# power_dist.net
KiCad netlist of a schematic drawn in EAGLE
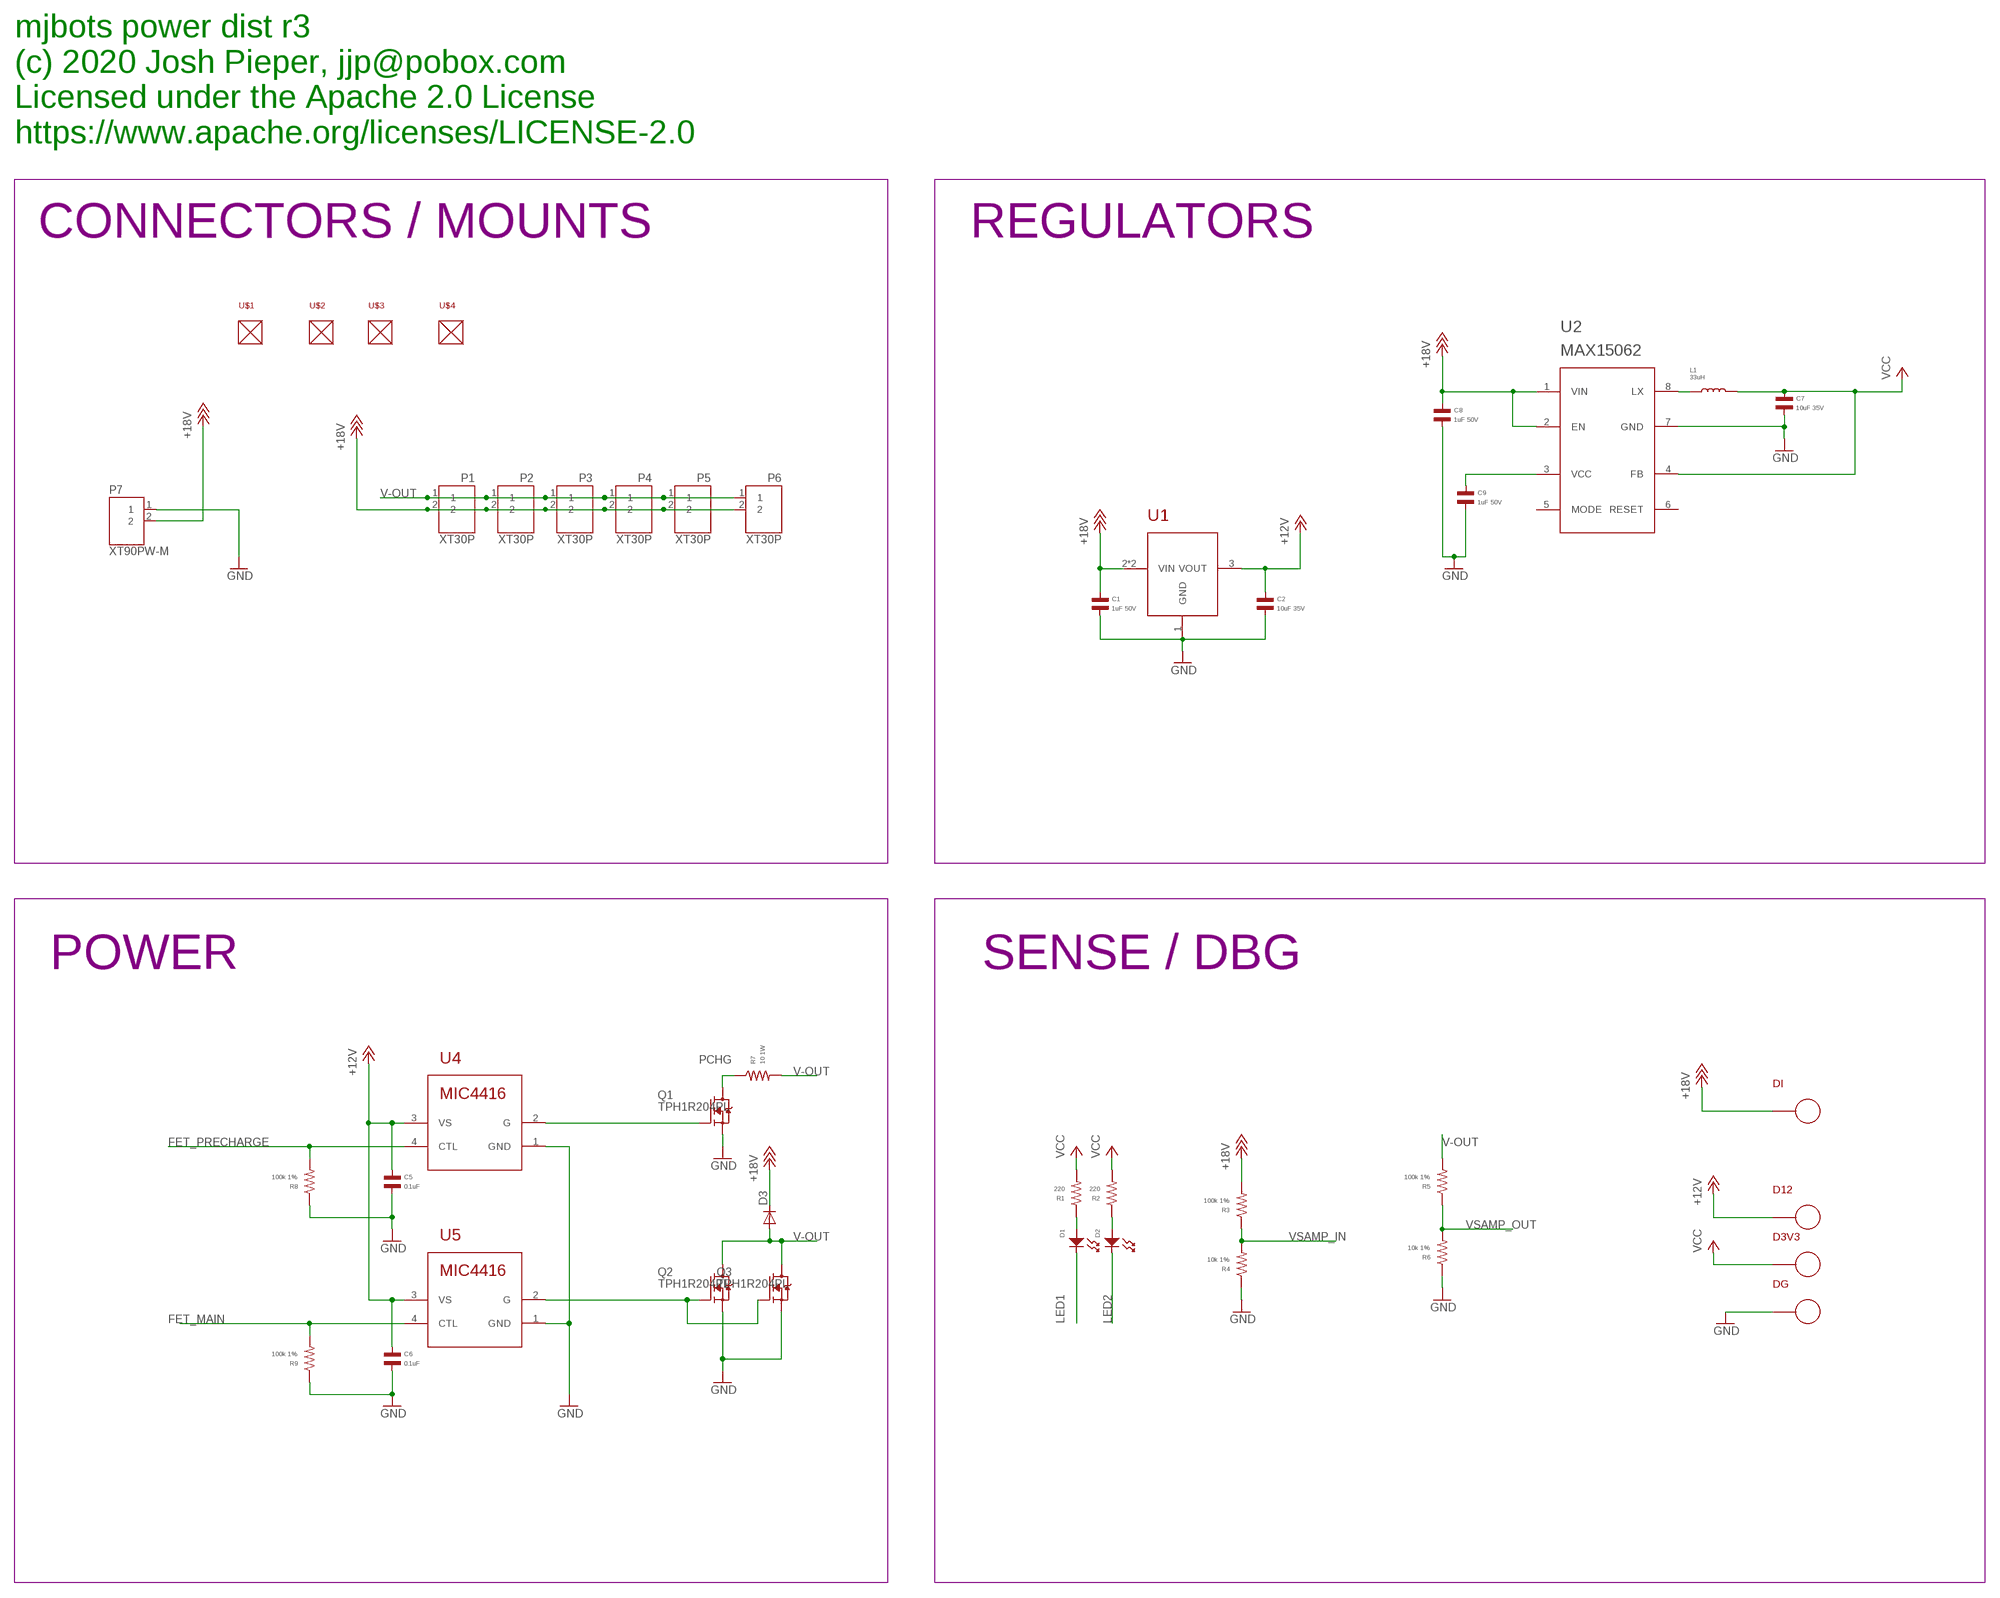
[diagram p0: schematic, sheet 1, part 1 of 2]
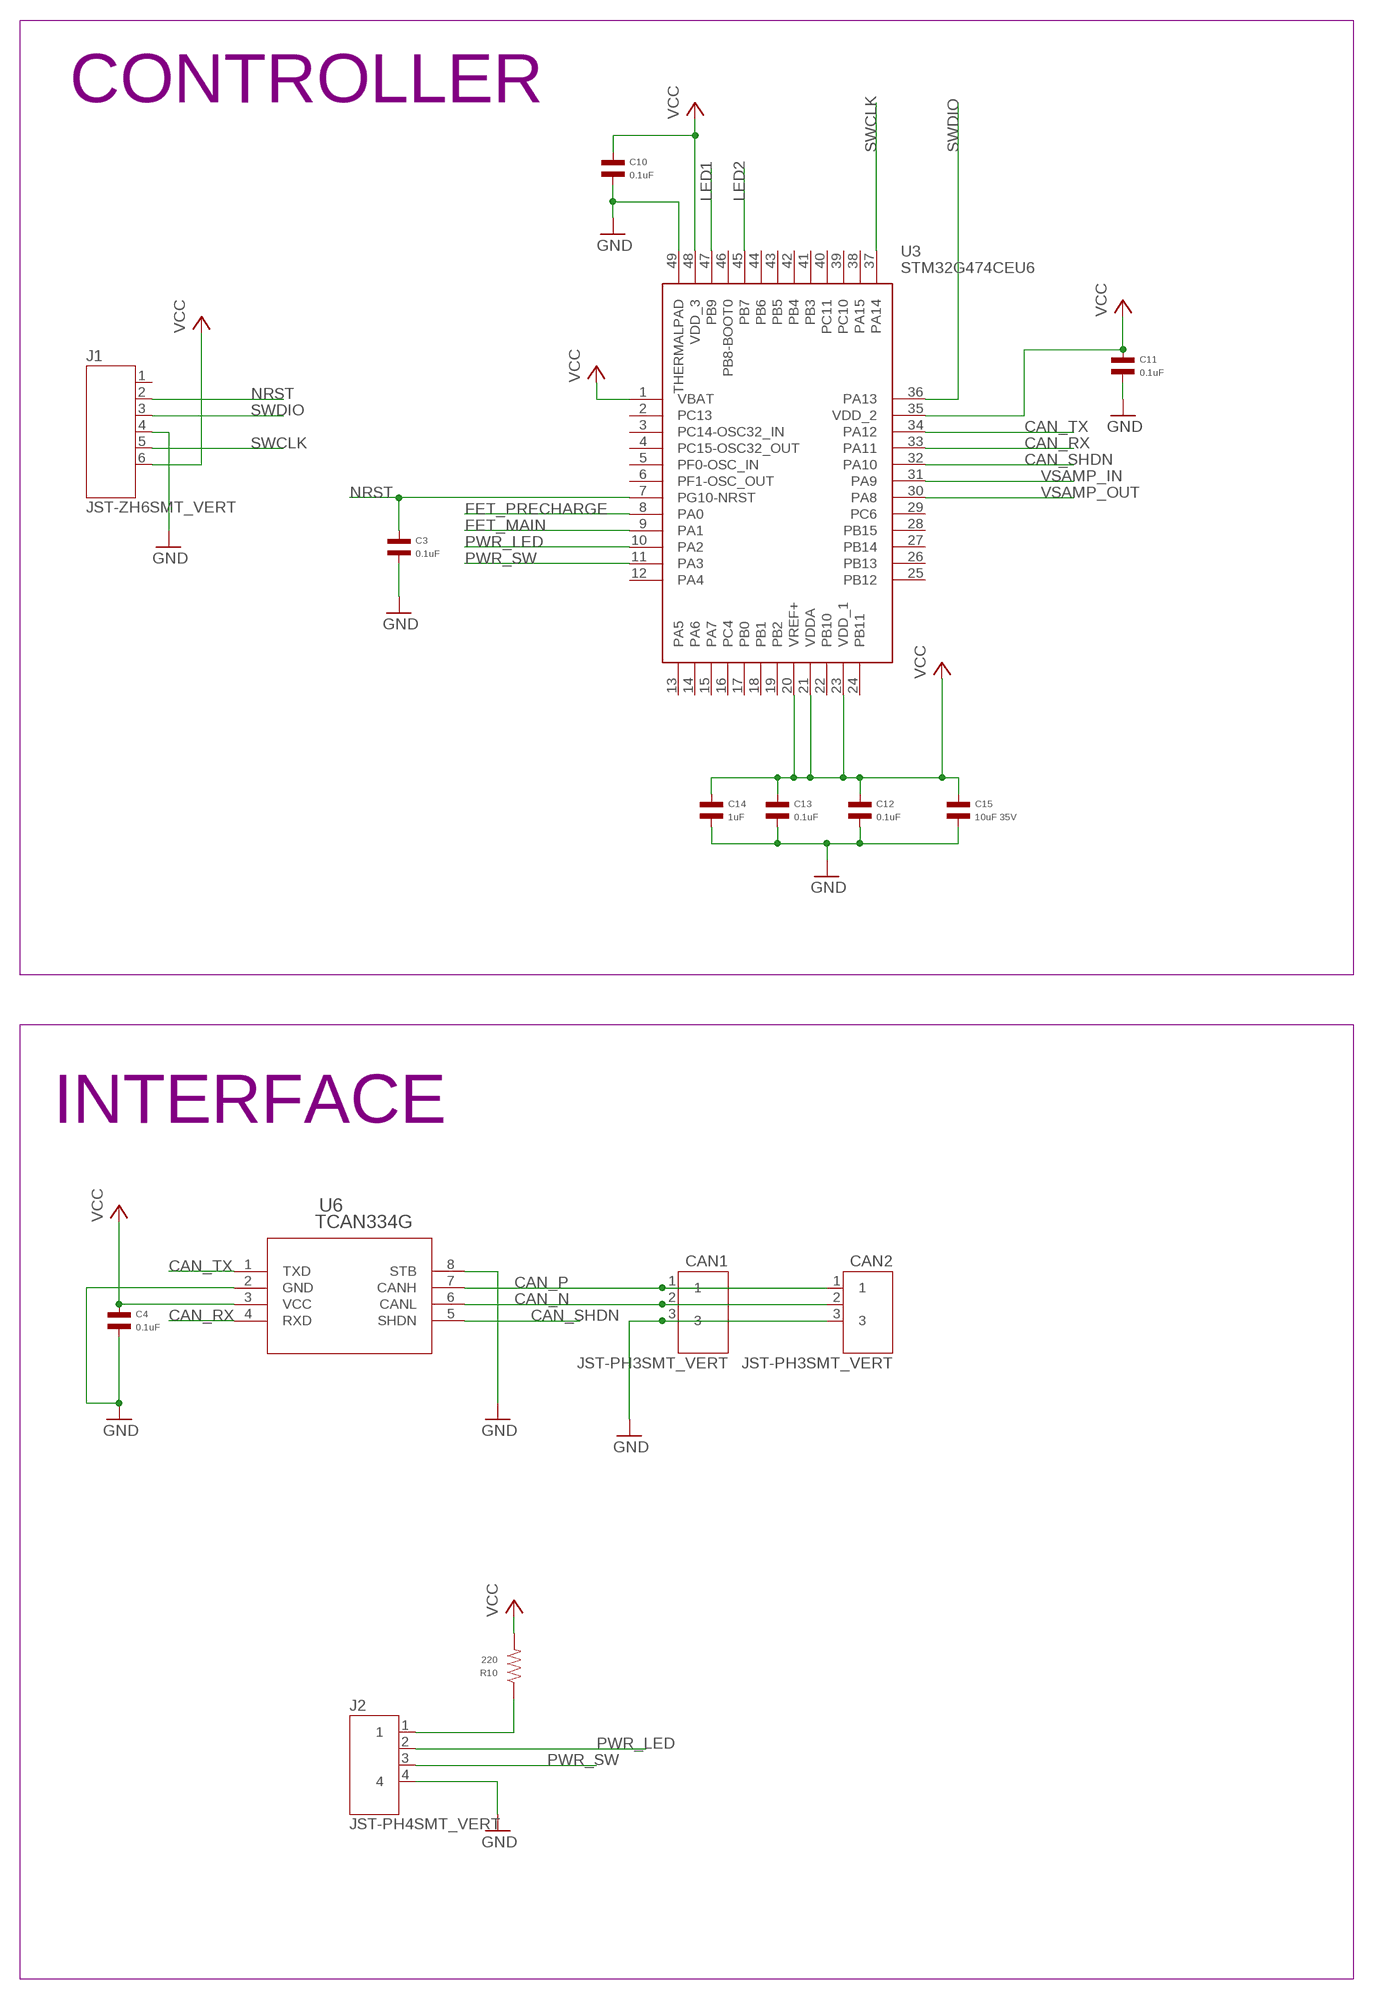
[diagram p1: schematic, sheet 1, part 2 of 2]

(export (version "E")
  (design (tool "Eeschema 10.0.6"))
  (components
    (comp (ref "C1")
      (value "1uF 50V")
      (footprint "eagle-import:C0603")
      (fields (field (name "MF") "SAMSUNG") (field (name "MPN") "CL10A105KB8NNNC"))
      (libsource (lib "eagle-import") (part "CAPACITOR_NP_0603"))
    )
    (comp (ref "C2")
      (value "10uF 35V")
      (footprint "eagle-import:C1206")
      (fields (field (name "MF") "TDK") (field (name "MPN") "CGA5L1X7R1V106K160AC"))
      (libsource (lib "eagle-import") (part "CAPACITOR_NP_1206"))
    )
    (comp (ref "C3")
      (value "0.1uF")
      (footprint "eagle-import:C0402")
      (fields (field (name "HOUSEPART") "1") (field (name "MPN") "MF-CAP-0402-0.1uF"))
      (libsource (lib "eagle-import") (part "CAPACITOR_NP_0402"))
    )
    (comp (ref "C4")
      (value "0.1uF")
      (footprint "eagle-import:C0402")
      (fields (field (name "HOUSEPART") "1") (field (name "MPN") "MF-CAP-0402-0.1uF"))
      (libsource (lib "eagle-import") (part "CAPACITOR_NP_0402"))
    )
    (comp (ref "C5")
      (value "0.1uF")
      (footprint "eagle-import:C0402")
      (fields (field (name "HOUSEPART") "1") (field (name "MPN") "MF-CAP-0402-0.1uF"))
      (libsource (lib "eagle-import") (part "CAPACITOR_NP_0402"))
    )
    (comp (ref "C6")
      (value "0.1uF")
      (footprint "eagle-import:C0402")
      (fields (field (name "HOUSEPART") "1") (field (name "MPN") "MF-CAP-0402-0.1uF"))
      (libsource (lib "eagle-import") (part "CAPACITOR_NP_0402"))
    )
    (comp (ref "C7")
      (value "10uF 35V")
      (footprint "eagle-import:C1206")
      (fields (field (name "MF") "TDK") (field (name "MPN") "CGA5L1X7R1V106K160AC"))
      (libsource (lib "eagle-import") (part "CAPACITOR_NP_1206"))
    )
    (comp (ref "C8")
      (value "1uF 50V")
      (footprint "eagle-import:C0603")
      (fields (field (name "MF") "SAMSUNG") (field (name "MPN") "CL10A105KB8NNNC"))
      (libsource (lib "eagle-import") (part "CAPACITOR_NP_0603"))
    )
    (comp (ref "C9")
      (value "1uF 50V")
      (footprint "eagle-import:C0603")
      (fields (field (name "MF") "SAMSUNG") (field (name "MPN") "CL10A105KB8NNNC"))
      (libsource (lib "eagle-import") (part "CAPACITOR_NP_0603"))
    )
    (comp (ref "C10")
      (value "0.1uF")
      (footprint "eagle-import:C0402")
      (fields (field (name "HOUSEPART") "1") (field (name "MPN") "MF-CAP-0402-0.1uF"))
      (libsource (lib "eagle-import") (part "CAPACITOR_NP_0402"))
    )
    (comp (ref "C11")
      (value "0.1uF")
      (footprint "eagle-import:C0402")
      (fields (field (name "HOUSEPART") "1") (field (name "MPN") "MF-CAP-0402-0.1uF"))
      (libsource (lib "eagle-import") (part "CAPACITOR_NP_0402"))
    )
    (comp (ref "C12")
      (value "0.1uF")
      (footprint "eagle-import:C0402")
      (fields (field (name "HOUSEPART") "1") (field (name "MPN") "MF-CAP-0402-0.1uF"))
      (libsource (lib "eagle-import") (part "CAPACITOR_NP_0402"))
    )
    (comp (ref "C13")
      (value "0.1uF")
      (footprint "eagle-import:C0402")
      (fields (field (name "HOUSEPART") "1") (field (name "MPN") "MF-CAP-0402-0.1uF"))
      (libsource (lib "eagle-import") (part "CAPACITOR_NP_0402"))
    )
    (comp (ref "C14")
      (value "1uF")
      (footprint "eagle-import:C0402")
      (fields (field (name "HOUSEPART") "1") (field (name "MPN") "MF-CAP-0402-1uF"))
      (libsource (lib "eagle-import") (part "CAPACITOR_NP_0402"))
    )
    (comp (ref "C15")
      (value "10uF 35V")
      (footprint "eagle-import:C1206")
      (fields (field (name "MF") "TDK") (field (name "MPN") "CGA5L1X7R1V106K160AC"))
      (libsource (lib "eagle-import") (part "CAPACITOR_NP_1206"))
    )
    (comp (ref "CAN1")
      (value "JST-PH3SMT_VERT")
      (footprint "eagle-import:JST_B3B_PH-SM4-TB(LF)(SN)")
      (fields (field (name "MF") "JST") (field (name "MPN") "B3B-PH-SM4-TB(LF)(SN)"))
      (libsource (lib "eagle-import") (part "JST-PH3SMT_VERT"))
    )
    (comp (ref "CAN2")
      (value "JST-PH3SMT_VERT")
      (footprint "eagle-import:JST_B3B_PH-SM4-TB(LF)(SN)")
      (fields (field (name "MF") "JST") (field (name "MPN") "B3B-PH-SM4-TB(LF)(SN)"))
      (libsource (lib "eagle-import") (part "JST-PH3SMT_VERT"))
    )
    (comp (ref "D1")
      (value "LED_SINGLE-0603")
      (footprint "eagle-import:LED0603")
      (fields
        (field (name "HOUSEPART") "NO")
        (field (name "HOUSEPART_1") "1")
        (field (name "MPN") "MF-LED-0603-RED")
      )
      (libsource (lib "eagle-import") (part "LED_SINGLE-0603"))
    )
    (comp (ref "D2")
      (value "LED_SINGLE-0603")
      (footprint "eagle-import:LED0603")
      (fields
        (field (name "HOUSEPART") "NO")
        (field (name "HOUSEPART_1") "1")
        (field (name "MPN") "MF-LED-0603-RED")
      )
      (libsource (lib "eagle-import") (part "LED_SINGLE-0603"))
    )
    (comp (ref "D3")
      (value "DIODE-")
      (footprint "eagle-import:DO-214AB")
      (fields (field (name "MF") "MICRO COMMERCIAL") (field (name "MPN") "SK510L-TP"))
      (libsource (lib "eagle-import") (part "DIODE-"))
    )
    (comp (ref "D3V3")
      (value "PAD24AWG_PAD")
      (footprint "eagle-import:24AWG_PAD")
      (libsource (lib "eagle-import") (part "PAD24AWG_PAD"))
    )
    (comp (ref "D12")
      (value "PAD24AWG_PAD")
      (footprint "eagle-import:24AWG_PAD")
      (libsource (lib "eagle-import") (part "PAD24AWG_PAD"))
    )
    (comp (ref "DG")
      (value "PAD24AWG_PAD")
      (footprint "eagle-import:24AWG_PAD")
      (libsource (lib "eagle-import") (part "PAD24AWG_PAD"))
    )
    (comp (ref "DI")
      (value "PAD24AWG_PAD")
      (footprint "eagle-import:24AWG_PAD")
      (libsource (lib "eagle-import") (part "PAD24AWG_PAD"))
    )
    (comp (ref "J1")
      (value "JST-ZH6SMT_VERT")
      (footprint "eagle-import:JST_B6B-ZR-SM4-TF(LF)(SN)")
      (fields (field (name "MF") "JST") (field (name "MPN") "B6B-ZR-SM4-TF(LF)(SN)"))
      (libsource (lib "eagle-import") (part "JST-ZH6SMT_VERT"))
    )
    (comp (ref "J2")
      (value "JST-PH4SMT_VERT")
      (footprint "eagle-import:JST_B4B_PH-SM4-TB(LF)(SN)")
      (fields (field (name "MF") "JST") (field (name "MPN") "B4B-PH-SM4-TB(LF)(SN)"))
      (libsource (lib "eagle-import") (part "JST-PH4SMT_VERT"))
    )
    (comp (ref "L1")
      (value "33uH")
      (footprint "eagle-import:L1210")
      (fields (field (name "MF") "TDK") (field (name "MPN") "NLFV32T-330K-EF") (field (name "POPULATE") "1"))
      (libsource (lib "eagle-import") (part "INDUCTOR_1210"))
    )
    (comp (ref "P1")
      (value "XT30P")
      (footprint "eagle-import:XT30P")
      (libsource (lib "eagle-import") (part "XT30P"))
    )
    (comp (ref "P2")
      (value "XT30P")
      (footprint "eagle-import:XT30P")
      (libsource (lib "eagle-import") (part "XT30P"))
    )
    (comp (ref "P3")
      (value "XT30P")
      (footprint "eagle-import:XT30P")
      (libsource (lib "eagle-import") (part "XT30P"))
    )
    (comp (ref "P4")
      (value "XT30P")
      (footprint "eagle-import:XT30P")
      (libsource (lib "eagle-import") (part "XT30P"))
    )
    (comp (ref "P5")
      (value "XT30P")
      (footprint "eagle-import:XT30P")
      (libsource (lib "eagle-import") (part "XT30P"))
    )
    (comp (ref "P6")
      (value "XT30P")
      (footprint "eagle-import:XT30P")
      (libsource (lib "eagle-import") (part "XT30P"))
    )
    (comp (ref "P7")
      (value "XT90PW-M")
      (footprint "eagle-import:XT90PW-M")
      (libsource (lib "eagle-import") (part "XT90PW-M"))
    )
    (comp (ref "Q1")
      (value "TPH1R204PL")
      (footprint "eagle-import:SOP_ADVANCE")
      (fields (field (name "MF") "Toshiba") (field (name "MPN") "TPH1R204PL,L1Q"))
      (libsource (lib "eagle-import") (part "TPH1R204PL"))
    )
    (comp (ref "Q2")
      (value "TPH1R204PL")
      (footprint "eagle-import:SOP_ADVANCE")
      (fields (field (name "MF") "Toshiba") (field (name "MPN") "TPH1R204PL,L1Q"))
      (libsource (lib "eagle-import") (part "TPH1R204PL"))
    )
    (comp (ref "Q3")
      (value "TPH1R204PL")
      (footprint "eagle-import:SOP_ADVANCE")
      (fields (field (name "MF") "Toshiba") (field (name "MPN") "TPH1R204PL,L1Q"))
      (libsource (lib "eagle-import") (part "TPH1R204PL"))
    )
    (comp (ref "R1")
      (value "220")
      (footprint "eagle-import:R0603")
      (fields (field (name "HOUSEPART") "1") (field (name "MPN") "MF-RES-0603-220"))
      (libsource (lib "eagle-import") (part "RESISTOR_0603"))
    )
    (comp (ref "R2")
      (value "220")
      (footprint "eagle-import:R0603")
      (fields (field (name "HOUSEPART") "1") (field (name "MPN") "MF-RES-0603-220"))
      (libsource (lib "eagle-import") (part "RESISTOR_0603"))
    )
    (comp (ref "R3")
      (value "100k 1%")
      (footprint "eagle-import:R0603")
      (fields (field (name "MF") "VISHAY") (field (name "MPN") "CRCW0603100KFKEA"))
      (libsource (lib "eagle-import") (part "RESISTOR_0603"))
    )
    (comp (ref "R4")
      (value "10k 1%")
      (footprint "eagle-import:R0603")
      (fields (field (name "MF") "PANASONIC") (field (name "MPN") "ERJ-3EKF1002V"))
      (libsource (lib "eagle-import") (part "RESISTOR_0603"))
    )
    (comp (ref "R5")
      (value "100k 1%")
      (footprint "eagle-import:R0603")
      (fields (field (name "MF") "VISHAY") (field (name "MPN") "CRCW0603100KFKEA"))
      (libsource (lib "eagle-import") (part "RESISTOR_0603"))
    )
    (comp (ref "R6")
      (value "10k 1%")
      (footprint "eagle-import:R0603")
      (fields (field (name "MF") "PANASONIC") (field (name "MPN") "ERJ-3EKF1002V"))
      (libsource (lib "eagle-import") (part "RESISTOR_0603"))
    )
    (comp (ref "R7")
      (value "10 1W")
      (footprint "eagle-import:R1206")
      (fields (field (name "MF") "Susumu") (field (name "MPN") "HRG3216Q-10R0-D-T1"))
      (libsource (lib "eagle-import") (part "RESISTOR_1206"))
    )
    (comp (ref "R8")
      (value "100k 1%")
      (footprint "eagle-import:R0603")
      (fields (field (name "MF") "VISHAY") (field (name "MPN") "CRCW0603100KFKEA"))
      (libsource (lib "eagle-import") (part "RESISTOR_0603"))
    )
    (comp (ref "R9")
      (value "100k 1%")
      (footprint "eagle-import:R0603")
      (fields (field (name "MF") "VISHAY") (field (name "MPN") "CRCW0603100KFKEA"))
      (libsource (lib "eagle-import") (part "RESISTOR_0603"))
    )
    (comp (ref "R10")
      (value "220")
      (footprint "eagle-import:R0603")
      (fields (field (name "HOUSEPART") "1") (field (name "MPN") "MF-RES-0603-220"))
      (libsource (lib "eagle-import") (part "RESISTOR_0603"))
    )
    (comp (ref "U$1")
      (value "MOUNT")
      (footprint "eagle-import:M2.5MOUNT")
      (libsource (lib "eagle-import") (part "MOUNT"))
    )
    (comp (ref "U$2")
      (value "MOUNT")
      (footprint "eagle-import:M2.5MOUNT")
      (libsource (lib "eagle-import") (part "MOUNT"))
    )
    (comp (ref "U$3")
      (value "MOUNT")
      (footprint "eagle-import:M2.5MOUNT")
      (libsource (lib "eagle-import") (part "MOUNT"))
    )
    (comp (ref "U$4")
      (value "MOUNT")
      (footprint "eagle-import:M2.5MOUNT")
      (libsource (lib "eagle-import") (part "MOUNT"))
    )
    (comp (ref "U1")
      (value "ZXTR2012Z")
      (footprint "eagle-import:SOT89")
      (fields (field (name "MF") "DIODES INC") (field (name "MPN") "ZXTR2012Z-13"))
      (libsource (lib "eagle-import") (part "ZXTR2012Z"))
    )
    (comp (ref "U2")
      (value "MAX150628TDFN")
      (footprint "eagle-import:8TDFN")
      (fields (field (name "MF") "MAXIM") (field (name "MPN") "MAX15062AATA+T"))
      (libsource (lib "eagle-import") (part "MAX150628TDFN"))
    )
    (comp (ref "U3")
      (value "STM32G474CEU6")
      (footprint "eagle-import:QFN50P700X700X60-49N")
      (fields (field (name "MOUSER_PART_NUMBER") "511-STM32G474CEU6") (field (name "MF") "ST"))
      (libsource (lib "eagle-import") (part "STM32G474CEU6"))
    )
    (comp (ref "U4")
      (value "MIC4416")
      (footprint "eagle-import:SOT143")
      (fields (field (name "MF") "MICROCHIP") (field (name "MPN") "MIC4416YM4-TR"))
      (libsource (lib "eagle-import") (part "MIC4416"))
    )
    (comp (ref "U5")
      (value "MIC4416")
      (footprint "eagle-import:SOT143")
      (fields (field (name "MF") "MICROCHIP") (field (name "MPN") "MIC4416YM4-TR"))
      (libsource (lib "eagle-import") (part "MIC4416"))
    )
    (comp (ref "U6")
      (value "TCAN334G")
      (footprint "eagle-import:SOIC8")
      (fields (field (name "MF") "TI") (field (name "MPN") "TCAN334GDR"))
      (libsource (lib "eagle-import") (part "TCAN334G"))
    )
  )
  (nets
    (net (code "1") (name "+12V") (class "Default")
      (node (ref "C2") (pin "P$1") (pinfunction "P$1_P$1") (pintype "passive"))
      (node (ref "C5") (pin "P$1") (pinfunction "P$1_P$1") (pintype "passive"))
      (node (ref "C6") (pin "P$1") (pinfunction "P$1_P$1") (pintype "passive"))
      (node (ref "D12") (pin "P$1") (pinfunction "P$1_P$1") (pintype "bidirectional"))
      (node (ref "U1") (pin "3") (pinfunction "VOUT_3") (pintype "bidirectional"))
      (node (ref "U4") (pin "3") (pinfunction "VS_3") (pintype "bidirectional"))
      (node (ref "U5") (pin "3") (pinfunction "VS_3") (pintype "bidirectional"))
    )
    (net (code "2") (name "+18V") (class "Default")
      (node (ref "C1") (pin "P$1") (pinfunction "P$1_P$1") (pintype "passive"))
      (node (ref "C8") (pin "P$1") (pinfunction "P$1_P$1") (pintype "passive"))
      (node (ref "D3") (pin "C") (pinfunction "C_C") (pintype "passive"))
      (node (ref "DI") (pin "P$1") (pinfunction "P$1_P$1") (pintype "bidirectional"))
      (node (ref "P1") (pin "2") (pinfunction "2_2") (pintype "passive"))
      (node (ref "P2") (pin "2") (pinfunction "2_2") (pintype "passive"))
      (node (ref "P3") (pin "2") (pinfunction "2_2") (pintype "passive"))
      (node (ref "P4") (pin "2") (pinfunction "2_2") (pintype "passive"))
      (node (ref "P5") (pin "2") (pinfunction "2_2") (pintype "passive"))
      (node (ref "P6") (pin "2") (pinfunction "2_2") (pintype "passive"))
      (node (ref "P7") (pin "2") (pinfunction "2_2") (pintype "passive"))
      (node (ref "R3") (pin "P$2") (pinfunction "P$2_P$2") (pintype "passive"))
      (node (ref "U1") (pin "2") (pinfunction "VIN_2") (pintype "bidirectional"))
      (node (ref "U1") (pin "PAD") (pinfunction "VIN_PAD") (pintype "bidirectional"))
      (node (ref "U2") (pin "1") (pinfunction "VIN_1") (pintype "passive"))
      (node (ref "U2") (pin "2") (pinfunction "EN_2") (pintype "passive"))
    )
    (net (code "3") (name "/CAN_N") (class "Default")
      (node (ref "CAN1") (pin "2") (pinfunction "2_2") (pintype "passive"))
      (node (ref "CAN2") (pin "2") (pinfunction "2_2") (pintype "passive"))
      (node (ref "U6") (pin "6") (pinfunction "CANL_6") (pintype "bidirectional"))
    )
    (net (code "4") (name "/CAN_P") (class "Default")
      (node (ref "CAN1") (pin "1") (pinfunction "1_1") (pintype "passive"))
      (node (ref "CAN2") (pin "1") (pinfunction "1_1") (pintype "passive"))
      (node (ref "U6") (pin "7") (pinfunction "CANH_7") (pintype "bidirectional"))
    )
    (net (code "5") (name "/CAN_RX") (class "Default")
      (node (ref "U3") (pin "33") (pinfunction "PA11_33") (pintype "bidirectional"))
      (node (ref "U6") (pin "4") (pinfunction "RXD_4") (pintype "output"))
    )
    (net (code "6") (name "/CAN_SHDN") (class "Default")
      (node (ref "U3") (pin "32") (pinfunction "PA10_32") (pintype "bidirectional"))
      (node (ref "U6") (pin "5") (pinfunction "SHDN_5") (pintype "input"))
    )
    (net (code "7") (name "/CAN_TX") (class "Default")
      (node (ref "U3") (pin "34") (pinfunction "PA12_34") (pintype "bidirectional"))
      (node (ref "U6") (pin "1") (pinfunction "TXD_1") (pintype "input"))
    )
    (net (code "8") (name "/FET_MAIN") (class "Default")
      (node (ref "R9") (pin "P$2") (pinfunction "P$2_P$2") (pintype "passive"))
      (node (ref "U3") (pin "9") (pinfunction "PA1_9") (pintype "bidirectional"))
      (node (ref "U5") (pin "4") (pinfunction "CTL_4") (pintype "bidirectional"))
    )
    (net (code "9") (name "/FET_PRECHARGE") (class "Default")
      (node (ref "R8") (pin "P$2") (pinfunction "P$2_P$2") (pintype "passive"))
      (node (ref "U3") (pin "8") (pinfunction "PA0_8") (pintype "bidirectional"))
      (node (ref "U4") (pin "4") (pinfunction "CTL_4") (pintype "bidirectional"))
    )
    (net (code "10") (name "/LED1") (class "Default")
      (node (ref "D1") (pin "CATHODE") (pinfunction "CATHODE_CATHODE") (pintype "power_in"))
      (node (ref "U3") (pin "47") (pinfunction "PB9_47") (pintype "bidirectional"))
    )
    (net (code "11") (name "/LED2") (class "Default")
      (node (ref "D2") (pin "CATHODE") (pinfunction "CATHODE_CATHODE") (pintype "power_in"))
      (node (ref "U3") (pin "45") (pinfunction "PB7_45") (pintype "bidirectional"))
    )
    (net (code "12") (name "/NRST") (class "Default")
      (node (ref "C3") (pin "P$1") (pinfunction "P$1_P$1") (pintype "passive"))
      (node (ref "J1") (pin "2") (pinfunction "2_2") (pintype "passive"))
      (node (ref "U3") (pin "7") (pinfunction "PG10-NRST_7") (pintype "bidirectional"))
    )
    (net (code "13") (name "/PCHG") (class "Default")
      (node (ref "Q1") (pin "5") (pinfunction "D_5") (pintype "passive"))
      (node (ref "Q1") (pin "6") (pinfunction "D_6") (pintype "passive"))
      (node (ref "Q1") (pin "7") (pinfunction "D_7") (pintype "passive"))
      (node (ref "Q1") (pin "8") (pinfunction "D_8") (pintype "passive"))
      (node (ref "Q1") (pin "PAD") (pinfunction "D_PAD") (pintype "passive"))
      (node (ref "R7") (pin "P$1") (pinfunction "P$1_P$1") (pintype "passive"))
    )
    (net (code "14") (name "/PWR_LED") (class "Default")
      (node (ref "J2") (pin "2") (pinfunction "2_2") (pintype "passive"))
      (node (ref "U3") (pin "10") (pinfunction "PA2_10") (pintype "bidirectional"))
    )
    (net (code "15") (name "/PWR_SW") (class "Default")
      (node (ref "J2") (pin "3") (pinfunction "3_3") (pintype "passive"))
      (node (ref "U3") (pin "11") (pinfunction "PA3_11") (pintype "bidirectional"))
    )
    (net (code "16") (name "/SWCLK") (class "Default")
      (node (ref "J1") (pin "5") (pinfunction "5_5") (pintype "passive"))
      (node (ref "U3") (pin "37") (pinfunction "PA14_37") (pintype "bidirectional"))
    )
    (net (code "17") (name "/SWDIO") (class "Default")
      (node (ref "J1") (pin "3") (pinfunction "3_3") (pintype "passive"))
      (node (ref "U3") (pin "36") (pinfunction "PA13_36") (pintype "bidirectional"))
    )
    (net (code "18") (name "/V-OUT") (class "Default")
      (node (ref "D3") (pin "A") (pinfunction "A_A") (pintype "passive"))
      (node (ref "P1") (pin "1") (pinfunction "1_1") (pintype "passive"))
      (node (ref "P2") (pin "1") (pinfunction "1_1") (pintype "passive"))
      (node (ref "P3") (pin "1") (pinfunction "1_1") (pintype "passive"))
      (node (ref "P4") (pin "1") (pinfunction "1_1") (pintype "passive"))
      (node (ref "P5") (pin "1") (pinfunction "1_1") (pintype "passive"))
      (node (ref "P6") (pin "1") (pinfunction "1_1") (pintype "passive"))
      (node (ref "Q2") (pin "5") (pinfunction "D_5") (pintype "passive"))
      (node (ref "Q2") (pin "6") (pinfunction "D_6") (pintype "passive"))
      (node (ref "Q2") (pin "7") (pinfunction "D_7") (pintype "passive"))
      (node (ref "Q2") (pin "8") (pinfunction "D_8") (pintype "passive"))
      (node (ref "Q2") (pin "PAD") (pinfunction "D_PAD") (pintype "passive"))
      (node (ref "Q3") (pin "5") (pinfunction "D_5") (pintype "passive"))
      (node (ref "Q3") (pin "6") (pinfunction "D_6") (pintype "passive"))
      (node (ref "Q3") (pin "7") (pinfunction "D_7") (pintype "passive"))
      (node (ref "Q3") (pin "8") (pinfunction "D_8") (pintype "passive"))
      (node (ref "Q3") (pin "PAD") (pinfunction "D_PAD") (pintype "passive"))
      (node (ref "R5") (pin "P$2") (pinfunction "P$2_P$2") (pintype "passive"))
      (node (ref "R7") (pin "P$2") (pinfunction "P$2_P$2") (pintype "passive"))
    )
    (net (code "19") (name "/VSAMP_IN") (class "Default")
      (node (ref "R3") (pin "P$1") (pinfunction "P$1_P$1") (pintype "passive"))
      (node (ref "R4") (pin "P$2") (pinfunction "P$2_P$2") (pintype "passive"))
      (node (ref "U3") (pin "31") (pinfunction "PA9_31") (pintype "bidirectional"))
    )
    (net (code "20") (name "/VSAMP_OUT") (class "Default")
      (node (ref "R5") (pin "P$1") (pinfunction "P$1_P$1") (pintype "passive"))
      (node (ref "R6") (pin "P$2") (pinfunction "P$2_P$2") (pintype "passive"))
      (node (ref "U3") (pin "30") (pinfunction "PA8_30") (pintype "bidirectional"))
    )
    (net (code "21") (name "GND") (class "Default")
      (node (ref "C1") (pin "P$2") (pinfunction "P$2_P$2") (pintype "passive"))
      (node (ref "C10") (pin "P$2") (pinfunction "P$2_P$2") (pintype "passive"))
      (node (ref "C11") (pin "P$2") (pinfunction "P$2_P$2") (pintype "passive"))
      (node (ref "C12") (pin "P$2") (pinfunction "P$2_P$2") (pintype "passive"))
      (node (ref "C13") (pin "P$2") (pinfunction "P$2_P$2") (pintype "passive"))
      (node (ref "C14") (pin "P$2") (pinfunction "P$2_P$2") (pintype "passive"))
      (node (ref "C15") (pin "P$2") (pinfunction "P$2_P$2") (pintype "passive"))
      (node (ref "C2") (pin "P$2") (pinfunction "P$2_P$2") (pintype "passive"))
      (node (ref "C3") (pin "P$2") (pinfunction "P$2_P$2") (pintype "passive"))
      (node (ref "C4") (pin "P$2") (pinfunction "P$2_P$2") (pintype "passive"))
      (node (ref "C5") (pin "P$2") (pinfunction "P$2_P$2") (pintype "passive"))
      (node (ref "C6") (pin "P$2") (pinfunction "P$2_P$2") (pintype "passive"))
      (node (ref "C7") (pin "P$2") (pinfunction "P$2_P$2") (pintype "passive"))
      (node (ref "C8") (pin "P$2") (pinfunction "P$2_P$2") (pintype "passive"))
      (node (ref "C9") (pin "P$2") (pinfunction "P$2_P$2") (pintype "passive"))
      (node (ref "CAN1") (pin "3") (pinfunction "3_3") (pintype "passive"))
      (node (ref "CAN2") (pin "3") (pinfunction "3_3") (pintype "passive"))
      (node (ref "DG") (pin "P$1") (pinfunction "P$1_P$1") (pintype "bidirectional"))
      (node (ref "J1") (pin "4") (pinfunction "4_4") (pintype "passive"))
      (node (ref "J2") (pin "4") (pinfunction "4_4") (pintype "passive"))
      (node (ref "P7") (pin "1") (pinfunction "1_1") (pintype "passive"))
      (node (ref "Q1") (pin "1") (pinfunction "S_1") (pintype "passive"))
      (node (ref "Q1") (pin "2") (pinfunction "S_2") (pintype "passive"))
      (node (ref "Q1") (pin "3") (pinfunction "S_3") (pintype "passive"))
      (node (ref "Q2") (pin "1") (pinfunction "S_1") (pintype "passive"))
      (node (ref "Q2") (pin "2") (pinfunction "S_2") (pintype "passive"))
      (node (ref "Q2") (pin "3") (pinfunction "S_3") (pintype "passive"))
      (node (ref "Q3") (pin "1") (pinfunction "S_1") (pintype "passive"))
      (node (ref "Q3") (pin "2") (pinfunction "S_2") (pintype "passive"))
      (node (ref "Q3") (pin "3") (pinfunction "S_3") (pintype "passive"))
      (node (ref "R4") (pin "P$1") (pinfunction "P$1_P$1") (pintype "passive"))
      (node (ref "R6") (pin "P$1") (pinfunction "P$1_P$1") (pintype "passive"))
      (node (ref "R8") (pin "P$1") (pinfunction "P$1_P$1") (pintype "passive"))
      (node (ref "R9") (pin "P$1") (pinfunction "P$1_P$1") (pintype "passive"))
      (node (ref "U1") (pin "1") (pinfunction "GND_1") (pintype "bidirectional"))
      (node (ref "U2") (pin "7") (pinfunction "GND_7") (pintype "passive"))
      (node (ref "U3") (pin "49") (pinfunction "THERMALPAD_49") (pintype "bidirectional"))
      (node (ref "U4") (pin "1") (pinfunction "GND_1") (pintype "bidirectional"))
      (node (ref "U5") (pin "1") (pinfunction "GND_1") (pintype "bidirectional"))
      (node (ref "U6") (pin "2") (pinfunction "GND_2") (pintype "power_in"))
      (node (ref "U6") (pin "8") (pinfunction "STB_8") (pintype "input"))
    )
    (net (code "22") (name "Net-(D1-PadANODE)") (class "Default")
      (node (ref "D1") (pin "ANODE") (pinfunction "ANODE_ANODE") (pintype "power_in"))
      (node (ref "R1") (pin "P$1") (pinfunction "P$1_P$1") (pintype "passive"))
    )
    (net (code "23") (name "Net-(D2-PadANODE)") (class "Default")
      (node (ref "D2") (pin "ANODE") (pinfunction "ANODE_ANODE") (pintype "power_in"))
      (node (ref "R2") (pin "P$1") (pinfunction "P$1_P$1") (pintype "passive"))
    )
    (net (code "24") (name "Net-(J2-Pad1)") (class "Default")
      (node (ref "J2") (pin "1") (pinfunction "1_1") (pintype "passive"))
      (node (ref "R10") (pin "P$1") (pinfunction "P$1_P$1") (pintype "passive"))
    )
    (net (code "25") (name "Net-(Q1-G)") (class "Default")
      (node (ref "Q1") (pin "4") (pinfunction "G_4") (pintype "passive"))
      (node (ref "U4") (pin "2") (pinfunction "G_2") (pintype "bidirectional"))
    )
    (net (code "26") (name "Net-(Q2-G)") (class "Default")
      (node (ref "Q2") (pin "4") (pinfunction "G_4") (pintype "passive"))
      (node (ref "Q3") (pin "4") (pinfunction "G_4") (pintype "passive"))
      (node (ref "U5") (pin "2") (pinfunction "G_2") (pintype "bidirectional"))
    )
    (net (code "27") (name "Net-(U2-LX)") (class "Default")
      (node (ref "L1") (pin "P$1") (pinfunction "P$1_P$1") (pintype "passive"))
      (node (ref "U2") (pin "8") (pinfunction "LX_8") (pintype "passive"))
    )
    (net (code "28") (name "Net-(U2-VCC)") (class "Default")
      (node (ref "C9") (pin "P$1") (pinfunction "P$1_P$1") (pintype "passive"))
      (node (ref "U2") (pin "3") (pinfunction "VCC_3") (pintype "passive"))
    )
    (net (code "29") (name "VCC") (class "Default")
      (node (ref "C10") (pin "P$1") (pinfunction "P$1_P$1") (pintype "passive"))
      (node (ref "C11") (pin "P$1") (pinfunction "P$1_P$1") (pintype "passive"))
      (node (ref "C12") (pin "P$1") (pinfunction "P$1_P$1") (pintype "passive"))
      (node (ref "C13") (pin "P$1") (pinfunction "P$1_P$1") (pintype "passive"))
      (node (ref "C14") (pin "P$1") (pinfunction "P$1_P$1") (pintype "passive"))
      (node (ref "C15") (pin "P$1") (pinfunction "P$1_P$1") (pintype "passive"))
      (node (ref "C4") (pin "P$1") (pinfunction "P$1_P$1") (pintype "passive"))
      (node (ref "C7") (pin "P$1") (pinfunction "P$1_P$1") (pintype "passive"))
      (node (ref "D3V3") (pin "P$1") (pinfunction "P$1_P$1") (pintype "bidirectional"))
      (node (ref "J1") (pin "6") (pinfunction "6_6") (pintype "passive"))
      (node (ref "L1") (pin "P$2") (pinfunction "P$2_P$2") (pintype "passive"))
      (node (ref "R1") (pin "P$2") (pinfunction "P$2_P$2") (pintype "passive"))
      (node (ref "R10") (pin "P$2") (pinfunction "P$2_P$2") (pintype "passive"))
      (node (ref "R2") (pin "P$2") (pinfunction "P$2_P$2") (pintype "passive"))
      (node (ref "U2") (pin "4") (pinfunction "FB_4") (pintype "passive"))
      (node (ref "U3") (pin "1") (pinfunction "VBAT_1") (pintype "bidirectional"))
      (node (ref "U3") (pin "20") (pinfunction "VREF+_20") (pintype "bidirectional"))
      (node (ref "U3") (pin "21") (pinfunction "VDDA_21") (pintype "bidirectional"))
      (node (ref "U3") (pin "23") (pinfunction "VDD_1_23") (pintype "bidirectional"))
      (node (ref "U3") (pin "35") (pinfunction "VDD_2_35") (pintype "bidirectional"))
      (node (ref "U3") (pin "48") (pinfunction "VDD_3_48") (pintype "bidirectional"))
      (node (ref "U6") (pin "3") (pinfunction "VCC_3") (pintype "power_in"))
    )
    (net (code "30") (name "unconnected-(J1-Pad1)") (class "Default")
      (node (ref "J1") (pin "1") (pinfunction "1_1") (pintype "passive"))
    )
    (net (code "31") (name "unconnected-(U2-MODE-Pad5)") (class "Default")
      (node (ref "U2") (pin "5") (pinfunction "MODE_5") (pintype "passive"))
    )
    (net (code "32") (name "unconnected-(U2-RESET-Pad6)") (class "Default")
      (node (ref "U2") (pin "6") (pinfunction "RESET_6") (pintype "passive"))
    )
    (net (code "33") (name "unconnected-(U3-PA4-Pad12)") (class "Default")
      (node (ref "U3") (pin "12") (pinfunction "PA4_12") (pintype "bidirectional"))
    )
    (net (code "34") (name "unconnected-(U3-PA5-Pad13)") (class "Default")
      (node (ref "U3") (pin "13") (pinfunction "PA5_13") (pintype "bidirectional"))
    )
    (net (code "35") (name "unconnected-(U3-PA6-Pad14)") (class "Default")
      (node (ref "U3") (pin "14") (pinfunction "PA6_14") (pintype "bidirectional"))
    )
    (net (code "36") (name "unconnected-(U3-PA7-Pad15)") (class "Default")
      (node (ref "U3") (pin "15") (pinfunction "PA7_15") (pintype "bidirectional"))
    )
    (net (code "37") (name "unconnected-(U3-PA15-Pad38)") (class "Default")
      (node (ref "U3") (pin "38") (pinfunction "PA15_38") (pintype "bidirectional"))
    )
    (net (code "38") (name "unconnected-(U3-PB0-Pad17)") (class "Default")
      (node (ref "U3") (pin "17") (pinfunction "PB0_17") (pintype "bidirectional"))
    )
    (net (code "39") (name "unconnected-(U3-PB1-Pad18)") (class "Default")
      (node (ref "U3") (pin "18") (pinfunction "PB1_18") (pintype "bidirectional"))
    )
    (net (code "40") (name "unconnected-(U3-PB2-Pad19)") (class "Default")
      (node (ref "U3") (pin "19") (pinfunction "PB2_19") (pintype "bidirectional"))
    )
    (net (code "41") (name "unconnected-(U3-PB3-Pad41)") (class "Default")
      (node (ref "U3") (pin "41") (pinfunction "PB3_41") (pintype "bidirectional"))
    )
    (net (code "42") (name "unconnected-(U3-PB4-Pad42)") (class "Default")
      (node (ref "U3") (pin "42") (pinfunction "PB4_42") (pintype "bidirectional"))
    )
    (net (code "43") (name "unconnected-(U3-PB5-Pad43)") (class "Default")
      (node (ref "U3") (pin "43") (pinfunction "PB5_43") (pintype "bidirectional"))
    )
    (net (code "44") (name "unconnected-(U3-PB6-Pad44)") (class "Default")
      (node (ref "U3") (pin "44") (pinfunction "PB6_44") (pintype "bidirectional"))
    )
    (net (code "45") (name "unconnected-(U3-PB8-BOOT0-Pad46)") (class "Default")
      (node (ref "U3") (pin "46") (pinfunction "PB8-BOOT0_46") (pintype "bidirectional"))
    )
    (net (code "46") (name "unconnected-(U3-PB10-Pad22)") (class "Default")
      (node (ref "U3") (pin "22") (pinfunction "PB10_22") (pintype "bidirectional"))
    )
    (net (code "47") (name "unconnected-(U3-PB11-Pad24)") (class "Default")
      (node (ref "U3") (pin "24") (pinfunction "PB11_24") (pintype "bidirectional"))
    )
    (net (code "48") (name "unconnected-(U3-PB12-Pad25)") (class "Default")
      (node (ref "U3") (pin "25") (pinfunction "PB12_25") (pintype "bidirectional"))
    )
    (net (code "49") (name "unconnected-(U3-PB13-Pad26)") (class "Default")
      (node (ref "U3") (pin "26") (pinfunction "PB13_26") (pintype "bidirectional"))
    )
    (net (code "50") (name "unconnected-(U3-PB14-Pad27)") (class "Default")
      (node (ref "U3") (pin "27") (pinfunction "PB14_27") (pintype "bidirectional"))
    )
    (net (code "51") (name "unconnected-(U3-PB15-Pad28)") (class "Default")
      (node (ref "U3") (pin "28") (pinfunction "PB15_28") (pintype "bidirectional"))
    )
    (net (code "52") (name "unconnected-(U3-PC4-Pad16)") (class "Default")
      (node (ref "U3") (pin "16") (pinfunction "PC4_16") (pintype "bidirectional"))
    )
    (net (code "53") (name "unconnected-(U3-PC6-Pad29)") (class "Default")
      (node (ref "U3") (pin "29") (pinfunction "PC6_29") (pintype "bidirectional"))
    )
    (net (code "54") (name "unconnected-(U3-PC10-Pad39)") (class "Default")
      (node (ref "U3") (pin "39") (pinfunction "PC10_39") (pintype "bidirectional"))
    )
    (net (code "55") (name "unconnected-(U3-PC11-Pad40)") (class "Default")
      (node (ref "U3") (pin "40") (pinfunction "PC11_40") (pintype "bidirectional"))
    )
    (net (code "56") (name "unconnected-(U3-PC13-Pad2)") (class "Default")
      (node (ref "U3") (pin "2") (pinfunction "PC13_2") (pintype "bidirectional"))
    )
    (net (code "57") (name "unconnected-(U3-PC14-OSC32_IN-Pad3)") (class "Default")
      (node (ref "U3") (pin "3") (pinfunction "PC14-OSC32_IN_3") (pintype "bidirectional"))
    )
    (net (code "58") (name "unconnected-(U3-PC15-OSC32_OUT-Pad4)") (class "Default")
      (node (ref "U3") (pin "4") (pinfunction "PC15-OSC32_OUT_4") (pintype "bidirectional"))
    )
    (net (code "59") (name "unconnected-(U3-PF0-OSC_IN-Pad5)") (class "Default")
      (node (ref "U3") (pin "5") (pinfunction "PF0-OSC_IN_5") (pintype "bidirectional"))
    )
    (net (code "60") (name "unconnected-(U3-PF1-OSC_OUT-Pad6)") (class "Default")
      (node (ref "U3") (pin "6") (pinfunction "PF1-OSC_OUT_6") (pintype "bidirectional"))
    )
  )
)
